# audio_amplifier.net
KiCad netlist of a schematic drawn in EAGLE
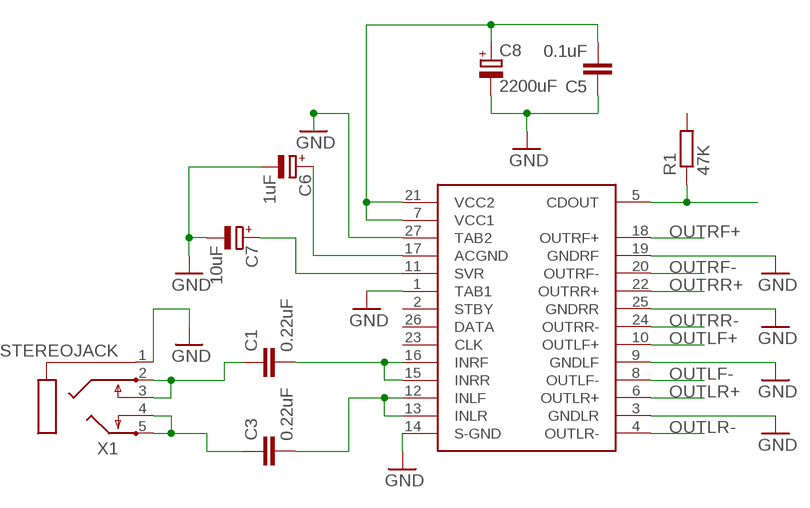
[diagram p0: schematic, sheet 1]

(export (version "E")
  (design (tool "Eeschema 10.0.6"))
  (components
    (comp (ref "C1")
      (value "0.22uF")
      (footprint "eagle-import:C025-024X044")
      (libsource (lib "eagle-import") (part "C-EU025-024X044"))
    )
    (comp (ref "C3")
      (value "0.22uF")
      (footprint "eagle-import:C025-024X044")
      (libsource (lib "eagle-import") (part "C-EU025-024X044"))
    )
    (comp (ref "C5")
      (value "0.1uF")
      (footprint "eagle-import:C025-024X044")
      (libsource (lib "eagle-import") (part "C-EU025-024X044"))
    )
    (comp (ref "C6")
      (value "1uF")
      (footprint "eagle-import:085CS_1AR")
      (libsource (lib "eagle-import") (part "CPOL-EU085CS-1AR"))
    )
    (comp (ref "C7")
      (value "10uF")
      (footprint "eagle-import:085CS_1AR")
      (libsource (lib "eagle-import") (part "CPOL-EU085CS-1AR"))
    )
    (comp (ref "C8")
      (value "2200uF")
      (footprint "eagle-import:085CS_1AR")
      (libsource (lib "eagle-import") (part "CPOL-EU085CS-1AR"))
    )
    (comp (ref "R1")
      (value "47K")
      (footprint "eagle-import:0204_5")
      (libsource (lib "eagle-import") (part "R-EU_0204/5"))
    )
    (comp (ref "TDA7563A")
      (value "TDA7563A")
      (footprint "eagle-import:TDA7563")
      (libsource (lib "eagle-import") (part "TDA7563A"))
    )
    (comp (ref "X1")
      (value "STEREOJACK")
      (footprint "eagle-import:STX3100")
      (libsource (lib "eagle-import") (part "STEREOJACK"))
    )
  )
  (nets
    (net (code "1") (name "/OUTLF+") (class "Default")
      (node (ref "TDA7563A") (pin "10") (pinfunction "OUTLF+_10") (pintype "bidirectional"))
    )
    (net (code "2") (name "/OUTLF-") (class "Default")
      (node (ref "TDA7563A") (pin "8") (pinfunction "OUTLF-_8") (pintype "bidirectional"))
    )
    (net (code "3") (name "/OUTLR+") (class "Default")
      (node (ref "TDA7563A") (pin "6") (pinfunction "OUTLR+_6") (pintype "bidirectional"))
    )
    (net (code "4") (name "/OUTLR-") (class "Default")
      (node (ref "TDA7563A") (pin "4") (pinfunction "OUTLR-_4") (pintype "bidirectional"))
    )
    (net (code "5") (name "/OUTRF+") (class "Default")
      (node (ref "TDA7563A") (pin "18") (pinfunction "OUTRF+_18") (pintype "bidirectional"))
    )
    (net (code "6") (name "/OUTRF-") (class "Default")
      (node (ref "TDA7563A") (pin "20") (pinfunction "OUTRF-_20") (pintype "bidirectional"))
    )
    (net (code "7") (name "/OUTRR+") (class "Default")
      (node (ref "TDA7563A") (pin "22") (pinfunction "OUTRR+_22") (pintype "bidirectional"))
    )
    (net (code "8") (name "/OUTRR-") (class "Default")
      (node (ref "TDA7563A") (pin "24") (pinfunction "OUTRR-_24") (pintype "bidirectional"))
    )
    (net (code "9") (name "GND") (class "Default")
      (node (ref "C5") (pin "1") (pinfunction "1_1") (pintype "passive"))
      (node (ref "C6") (pin "-") (pinfunction "-_-") (pintype "passive"))
      (node (ref "C7") (pin "-") (pinfunction "-_-") (pintype "passive"))
      (node (ref "C8") (pin "-") (pinfunction "-_-") (pintype "passive"))
      (node (ref "TDA7563A") (pin "1") (pinfunction "TAB1_1") (pintype "bidirectional"))
      (node (ref "TDA7563A") (pin "14") (pinfunction "S-GND_14") (pintype "bidirectional"))
      (node (ref "TDA7563A") (pin "19") (pinfunction "GNDRF_19") (pintype "bidirectional"))
      (node (ref "TDA7563A") (pin "25") (pinfunction "GNDRR_25") (pintype "bidirectional"))
      (node (ref "TDA7563A") (pin "27") (pinfunction "TAB2_27") (pintype "bidirectional"))
      (node (ref "TDA7563A") (pin "3") (pinfunction "GNDLR_3") (pintype "bidirectional"))
      (node (ref "TDA7563A") (pin "9") (pinfunction "GNDLF_9") (pintype "bidirectional"))
      (node (ref "X1") (pin "1") (pinfunction "1_1") (pintype "passive"))
    )
    (net (code "10") (name "Net-(C1-Pad1)") (class "Default")
      (node (ref "C1") (pin "1") (pinfunction "1_1") (pintype "passive"))
      (node (ref "X1") (pin "2") (pinfunction "2_2") (pintype "passive"))
      (node (ref "X1") (pin "3") (pinfunction "3_3") (pintype "passive"))
    )
    (net (code "11") (name "Net-(C3-Pad1)") (class "Default")
      (node (ref "C3") (pin "1") (pinfunction "1_1") (pintype "passive"))
      (node (ref "X1") (pin "4") (pinfunction "4_4") (pintype "passive"))
      (node (ref "X1") (pin "5") (pinfunction "5_5") (pintype "passive"))
    )
    (net (code "12") (name "Net-(TDA7563A-ACGND)") (class "Default")
      (node (ref "C6") (pin "+") (pinfunction "+_+") (pintype "passive"))
      (node (ref "TDA7563A") (pin "17") (pinfunction "ACGND_17") (pintype "bidirectional"))
    )
    (net (code "13") (name "Net-(TDA7563A-CDOUT)") (class "Default")
      (node (ref "R1") (pin "1") (pinfunction "1_1") (pintype "passive"))
      (node (ref "TDA7563A") (pin "5") (pinfunction "CDOUT_5") (pintype "bidirectional"))
    )
    (net (code "14") (name "Net-(TDA7563A-INLF)") (class "Default")
      (node (ref "C3") (pin "2") (pinfunction "2_2") (pintype "passive"))
      (node (ref "TDA7563A") (pin "12") (pinfunction "INLF_12") (pintype "bidirectional"))
      (node (ref "TDA7563A") (pin "13") (pinfunction "INLR_13") (pintype "bidirectional"))
    )
    (net (code "15") (name "Net-(TDA7563A-INRF)") (class "Default")
      (node (ref "C1") (pin "2") (pinfunction "2_2") (pintype "passive"))
      (node (ref "TDA7563A") (pin "15") (pinfunction "INRR_15") (pintype "bidirectional"))
      (node (ref "TDA7563A") (pin "16") (pinfunction "INRF_16") (pintype "bidirectional"))
    )
    (net (code "16") (name "Net-(TDA7563A-SVR)") (class "Default")
      (node (ref "C7") (pin "+") (pinfunction "+_+") (pintype "passive"))
      (node (ref "TDA7563A") (pin "11") (pinfunction "SVR_11") (pintype "bidirectional"))
    )
    (net (code "17") (name "Net-(TDA7563A-VCC1)") (class "Default")
      (node (ref "C5") (pin "2") (pinfunction "2_2") (pintype "passive"))
      (node (ref "C8") (pin "+") (pinfunction "+_+") (pintype "passive"))
      (node (ref "TDA7563A") (pin "21") (pinfunction "VCC2_21") (pintype "bidirectional"))
      (node (ref "TDA7563A") (pin "7") (pinfunction "VCC1_7") (pintype "input"))
    )
    (net (code "18") (name "unconnected-(R1-Pad2)") (class "Default")
      (node (ref "R1") (pin "2") (pinfunction "2_2") (pintype "passive"))
    )
    (net (code "19") (name "unconnected-(TDA7563A-CLK-Pad23)") (class "Default")
      (node (ref "TDA7563A") (pin "23") (pinfunction "CLK_23") (pintype "bidirectional"))
    )
    (net (code "20") (name "unconnected-(TDA7563A-DATA-Pad26)") (class "Default")
      (node (ref "TDA7563A") (pin "26") (pinfunction "DATA_26") (pintype "bidirectional"))
    )
    (net (code "21") (name "unconnected-(TDA7563A-STBY-Pad2)") (class "Default")
      (node (ref "TDA7563A") (pin "2") (pinfunction "STBY_2") (pintype "bidirectional"))
    )
  )
)
